# 05-AD9546_StrapsXtal.net
KiCad netlist of a schematic drawn in Altium Designer
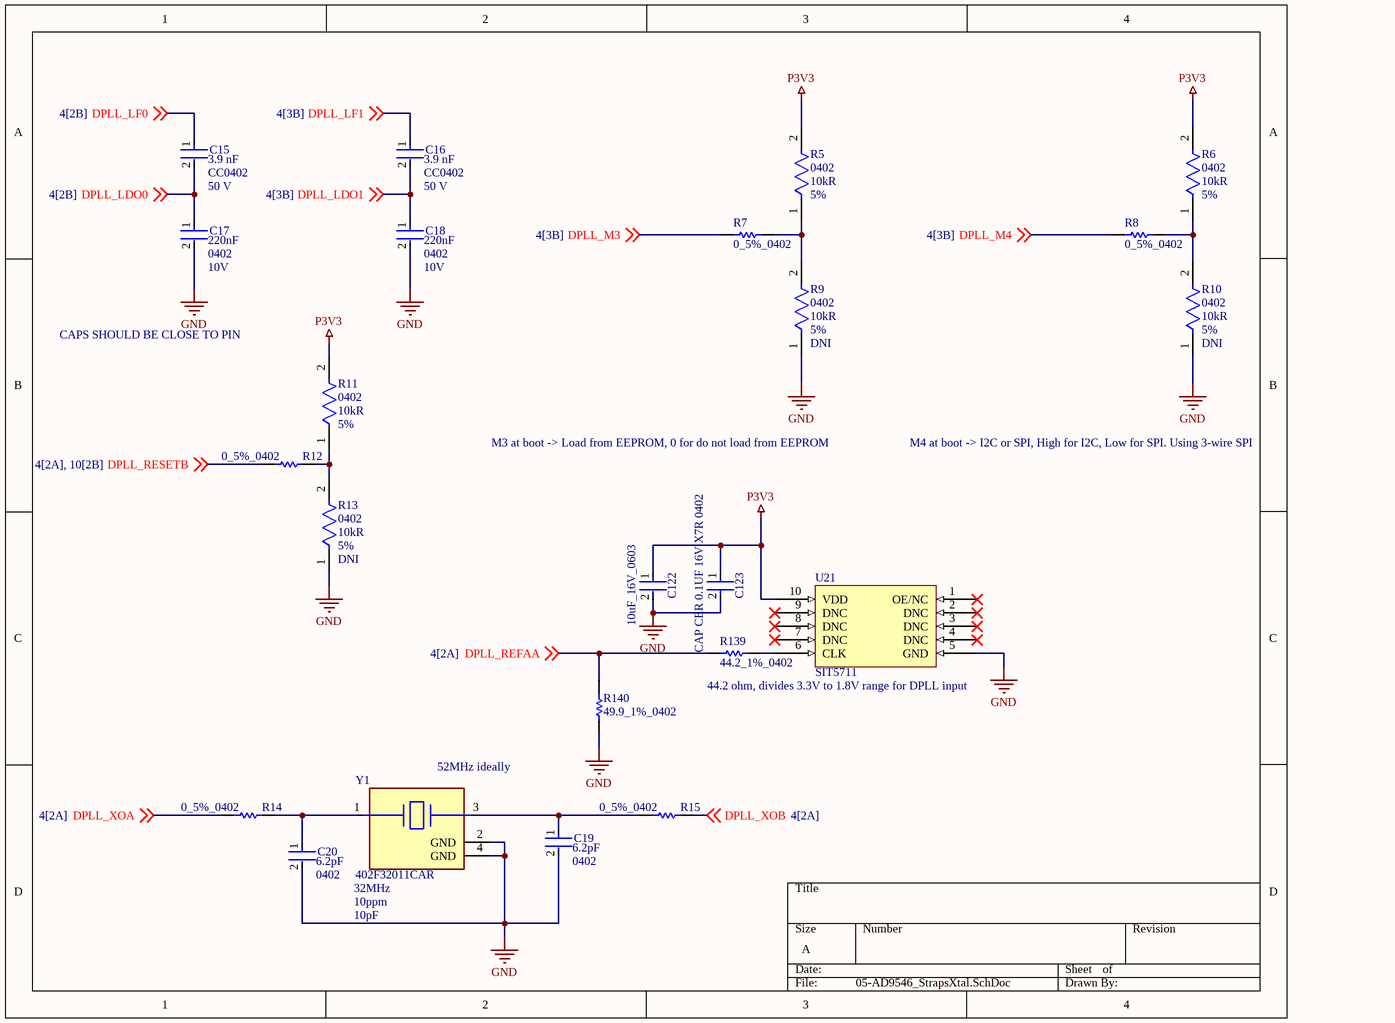
[diagram p0: 05-AD9546_StrapsXtal.SchDoc]

(export (version "E")
  (design (tool "Eeschema 10.0.6"))
  (components
    (comp (ref "C15")
      (value "3.9 nF")
      (footprint "FP-CC0402-MFG")
      (description "CAP CER 3900PF 50V X7R 0402")
      (fields
        (field (name "OCTOPART") "https://octopart.com/cc0402krx7r9bb392-yageo-9291741")
        (field (name "TOLERANCE") "0.1")
        (field (name "VOLTAGE RATING") "50 V")
        (field (name "PACKAGE") "CC0402")
      )
      (libsource (lib "Altium Content Vault") (part "11868f565c42a9108669ba33697ecf6"))
    )
    (comp (ref "C16")
      (value "3.9 nF")
      (footprint "FP-CC0402-MFG")
      (description "CAP CER 3900PF 50V X7R 0402")
      (fields
        (field (name "OCTOPART") "https://octopart.com/cc0402krx7r9bb392-yageo-9291741")
        (field (name "TOLERANCE") "0.1")
        (field (name "VOLTAGE RATING") "50 V")
        (field (name "PACKAGE") "CC0402")
      )
      (libsource (lib "Altium Content Vault") (part "11868f565c42a9108669ba33697ecf6"))
    )
    (comp (ref "C17")
      (value "GRM155R61A224KE19D")
      (footprint "FP-GRM155-0_05-IPC_A")
      (description "CAP CER 0.22UF 10V X5R 0402")
      (fields
        (field (name "VOLTAGE") "10V")
        (field (name "TOLERANCE") "10%")
        (field (name "CASE/PACKAGE") "0402")
        (field (name "CAPACITANCE") "220nF")
      )
      (libsource (lib "Altium Content Vault") (part "02cd4be3c70576c341d710602a673aa"))
    )
    (comp (ref "C18")
      (value "GRM155R61A224KE19D")
      (footprint "FP-GRM155-0_05-IPC_A")
      (description "CAP CER 0.22UF 10V X5R 0402")
      (fields
        (field (name "VOLTAGE") "10V")
        (field (name "TOLERANCE") "10%")
        (field (name "CASE/PACKAGE") "0402")
        (field (name "CAPACITANCE") "220nF")
      )
      (libsource (lib "Altium Content Vault") (part "02cd4be3c70576c341d710602a673aa"))
    )
    (comp (ref "C19")
      (value "CL05C6R2CB5NNNC")
      (footprint "FP-CL468-IPC_C")
      (description "Cap Ceramic 6.2pF 50V C0G ±0.25pF SMD 0402 +125°C Paper T/R")
      (fields (field (name "CASE/PACKAGE") "0402") (field (name "CAPACITANCE") "6.2pF"))
      (libsource (lib "Altium Content Vault") (part "b4654b650e69147ec39a6b967a45e02"))
    )
    (comp (ref "C20")
      (value "CL05C6R2CB5NNNC")
      (footprint "FP-CL468-IPC_C")
      (description "Cap Ceramic 6.2pF 50V C0G ±0.25pF SMD 0402 +125°C Paper T/R")
      (fields (field (name "CASE/PACKAGE") "0402") (field (name "CAPACITANCE") "6.2pF"))
      (libsource (lib "Altium Content Vault") (part "b4654b650e69147ec39a6b967a45e02"))
    )
    (comp (ref "C122")
      (value "10uF_16V_0603")
      (footprint "FP-C1608-MFG")
      (description "CAP CER 10UF 16V X5R 0603")
      (fields
        (field (name "OCTOPART") "https://octopart.com/c1608x5r1c106m080ab-tdk-26013480")
        (field (name "MANUFACTURER") "TDK Corporation")
      )
      (libsource (lib "Altium Content Vault") (part "11868f565c42a9108669ba33697ecf6"))
    )
    (comp (ref "C123")
      (value "GRM155R71C104KA88D")
      (footprint "FP-GRM15-MFG")
      (description "CAP CER 0.1UF 16V X7R 0402")
      (fields
        (field (name "TOLERANCE") "10%")
        (field (name "OCTOPART") "https://octopart.com/grm155r71c104ka88d-murata-196880")
        (field (name "DIGIKEY DESCRIPTION") "CAP CER 0.1UF 16V X7R 0402")
      )
      (libsource (lib "Altium Content Vault") (part "236180d848d6139a670b325ea6854c9"))
    )
    (comp (ref "R5")
      (value "CRCW040210K0JNED")
      (footprint "FP-CRCW0402-e3-IPC_B")
      (description "RES Thick Film, 10kΩ, 5%, 0.063W, 200ppm/°C, 0402")
      (fields
        (field (name "CASE/PACKAGE") "0402")
        (field (name "RESISTANCE") "10kR")
        (field (name "TOLERANCE") "5%")
      )
      (libsource (lib "Altium Content Vault") (part "1029c3af85768c4190bb7ad29bc67b5"))
    )
    (comp (ref "R6")
      (value "CRCW040210K0JNED")
      (footprint "FP-CRCW0402-e3-IPC_B")
      (description "RES Thick Film, 10kΩ, 5%, 0.063W, 200ppm/°C, 0402")
      (fields
        (field (name "CASE/PACKAGE") "0402")
        (field (name "RESISTANCE") "10kR")
        (field (name "TOLERANCE") "5%")
      )
      (libsource (lib "Altium Content Vault") (part "1029c3af85768c4190bb7ad29bc67b5"))
    )
    (comp (ref "R7")
      (value "0_5%_0402")
      (footprint "RESC1005X40X25ML05T10")
      (fields (field (name "PART NUMBER") "CRCW04020000Z0EDHP") (field (name "MANUFACTURER") "Vishay Dale"))
      (libsource (lib "Altium Content Vault") (part "RES"))
    )
    (comp (ref "R8")
      (value "0_5%_0402")
      (footprint "RESC1005X40X25ML05T10")
      (fields (field (name "PART NUMBER") "CRCW04020000Z0EDHP") (field (name "MANUFACTURER") "Vishay Dale"))
      (libsource (lib "Altium Content Vault") (part "RES"))
    )
    (comp (ref "R9")
      (value "CRCW040210K0JNED")
      (footprint "FP-CRCW0402-e3-IPC_B")
      (description "RES Thick Film, 10kΩ, 5%, 0.063W, 200ppm/°C, 0402")
      (fields
        (field (name "CASE/PACKAGE") "0402")
        (field (name "RESISTANCE") "10kR")
        (field (name "TOLERANCE") "5%")
        (field (name "DNI") "DNI")
      )
      (libsource (lib "Altium Content Vault") (part "1029c3af85768c4190bb7ad29bc67b5"))
    )
    (comp (ref "R10")
      (value "CRCW040210K0JNED")
      (footprint "FP-CRCW0402-e3-IPC_B")
      (description "RES Thick Film, 10kΩ, 5%, 0.063W, 200ppm/°C, 0402")
      (fields
        (field (name "CASE/PACKAGE") "0402")
        (field (name "RESISTANCE") "10kR")
        (field (name "TOLERANCE") "5%")
        (field (name "DNI") "DNI")
      )
      (libsource (lib "Altium Content Vault") (part "1029c3af85768c4190bb7ad29bc67b5"))
    )
    (comp (ref "R11")
      (value "CRCW040210K0JNED")
      (footprint "FP-CRCW0402-e3-IPC_B")
      (description "RES Thick Film, 10kΩ, 5%, 0.063W, 200ppm/°C, 0402")
      (fields
        (field (name "CASE/PACKAGE") "0402")
        (field (name "RESISTANCE") "10kR")
        (field (name "TOLERANCE") "5%")
      )
      (libsource (lib "Altium Content Vault") (part "1029c3af85768c4190bb7ad29bc67b5"))
    )
    (comp (ref "R12")
      (value "0_5%_0402")
      (footprint "RESC1005X40X25LL10T10")
      (fields (field (name "MANUFACTURER") "KOA Speer") (field (name "PART NUMBER") "RK73Z1ETTP"))
      (libsource (lib "Altium Content Vault") (part "RES"))
    )
    (comp (ref "R13")
      (value "CRCW040210K0JNED")
      (footprint "FP-CRCW0402-e3-IPC_B")
      (description "RES Thick Film, 10kΩ, 5%, 0.063W, 200ppm/°C, 0402")
      (fields
        (field (name "CASE/PACKAGE") "0402")
        (field (name "RESISTANCE") "10kR")
        (field (name "TOLERANCE") "5%")
        (field (name "DNI") "DNI")
      )
      (libsource (lib "Altium Content Vault") (part "1029c3af85768c4190bb7ad29bc67b5"))
    )
    (comp (ref "R14")
      (value "0_5%_0402")
      (footprint "RESC1005X40X25LL10T10")
      (fields (field (name "MANUFACTURER") "KOA Speer") (field (name "PART NUMBER") "RK73Z1ETTP"))
      (libsource (lib "Altium Content Vault") (part "RES"))
    )
    (comp (ref "R15")
      (value "0_5%_0402")
      (footprint "RESC1005X40X25LL10T10")
      (fields (field (name "MANUFACTURER") "KOA Speer") (field (name "PART NUMBER") "RK73Z1ETTP"))
      (libsource (lib "Altium Content Vault") (part "RES"))
    )
    (comp (ref "R139")
      (value "44.2_1%_0402")
      (footprint "RESC0402(1005)_M")
      (description "44R2 0.063W 1% 0402 (1005 Metric)  SMD")
      (fields (field (name "TOLERANCE") "1 %") (field (name "POWER") "0.063 W"))
      (libsource (lib "Altium Content Vault") (part "RES"))
    )
    (comp (ref "R140")
      (value "49.9_1%_0402")
      (footprint "RESC1005X40X25NL05T05")
      (fields (field (name "MANUFACTURER") "Panasonic") (field (name "PART NUMBER") "ERJ-2RKF49R9X"))
      (libsource (lib "Altium Content Vault") (part "RES"))
    )
    (comp (ref "U21")
      (value "SIT5711")
      (footprint "SIT5711")
      (libsource (lib "TimeDrive_Lib") (part "SIT5711"))
    )
    (comp (ref "Y1")
      (value "402F32011CAR")
      (footprint "FP-402-MFG")
      (description "CRYSTAL 32.0000MHZ 10PF SMD")
      (fields
        (field (name "FREQUENCY") "32MHz")
        (field (name "FREQUENCY STABILITY") "10ppm")
        (field (name "TOLERANCE") "10ppm")
        (field (name "LOAD CAPACITANCE") "10pF")
      )
      (libsource (lib "Altium Content Vault") (part "aa2bcc763e4d5c877d8ff97ea4c95a3"))
    )
  )
  (nets
    (net (code "1") (name "DPLL_LDO0") (class "Default")
      (node (ref "C15") (pin "2") (pinfunction "2_2") (pintype "passive"))
      (node (ref "C17") (pin "1") (pinfunction "1_1") (pintype "passive"))
    )
    (net (code "2") (name "DPLL_LDO1") (class "Default")
      (node (ref "C16") (pin "2") (pinfunction "2_2") (pintype "passive"))
      (node (ref "C18") (pin "1") (pinfunction "1_1") (pintype "passive"))
    )
    (net (code "3") (name "DPLL_LF0") (class "Default")
      (node (ref "C15") (pin "1") (pinfunction "1_1") (pintype "passive"))
    )
    (net (code "4") (name "DPLL_LF1") (class "Default")
      (node (ref "C16") (pin "1") (pinfunction "1_1") (pintype "passive"))
    )
    (net (code "5") (name "DPLL_M3") (class "Default")
      (node (ref "R7") (pin "1") (pinfunction "1_1") (pintype "passive"))
    )
    (net (code "6") (name "DPLL_M4") (class "Default")
      (node (ref "R8") (pin "1") (pinfunction "1_1") (pintype "passive"))
    )
    (net (code "7") (name "DPLL_REFAA") (class "Default")
      (node (ref "R139") (pin "1") (pinfunction "1_1") (pintype "passive"))
      (node (ref "R140") (pin "2") (pinfunction "2_2") (pintype "passive"))
    )
    (net (code "8") (name "DPLL_RESETB") (class "Default")
      (node (ref "R12") (pin "1") (pinfunction "1_1") (pintype "passive"))
    )
    (net (code "9") (name "DPLL_XOA") (class "Default")
      (node (ref "R14") (pin "1") (pinfunction "1_1") (pintype "passive"))
    )
    (net (code "10") (name "DPLL_XOB") (class "Default")
      (node (ref "R15") (pin "2") (pinfunction "2_2") (pintype "passive"))
    )
    (net (code "11") (name "GND") (class "Default")
      (node (ref "C122") (pin "2") (pinfunction "2_2") (pintype "passive"))
      (node (ref "C123") (pin "2") (pinfunction "2_2") (pintype "passive"))
      (node (ref "C17") (pin "2") (pinfunction "2_2") (pintype "passive"))
      (node (ref "C18") (pin "2") (pinfunction "2_2") (pintype "passive"))
      (node (ref "C19") (pin "2") (pinfunction "2_2") (pintype "passive"))
      (node (ref "C20") (pin "2") (pinfunction "2_2") (pintype "passive"))
      (node (ref "R10") (pin "1") (pinfunction "1_1") (pintype "passive"))
      (node (ref "R13") (pin "1") (pinfunction "1_1") (pintype "passive"))
      (node (ref "R140") (pin "1") (pinfunction "1_1") (pintype "passive"))
      (node (ref "R9") (pin "1") (pinfunction "1_1") (pintype "passive"))
      (node (ref "U21") (pin "5") (pinfunction "GND_5") (pintype "input"))
      (node (ref "Y1") (pin "2") (pinfunction "GND_2") (pintype "power_in"))
      (node (ref "Y1") (pin "4") (pinfunction "GND_4") (pintype "power_in"))
    )
    (net (code "12") (name "Net-(C19-Pad1)") (class "Default")
      (node (ref "C19") (pin "1") (pinfunction "1_1") (pintype "passive"))
      (node (ref "R15") (pin "1") (pinfunction "1_1") (pintype "passive"))
      (node (ref "Y1") (pin "3") (pinfunction "3_3") (pintype "passive"))
    )
    (net (code "13") (name "Net-(C20-Pad1)") (class "Default")
      (node (ref "C20") (pin "1") (pinfunction "1_1") (pintype "passive"))
      (node (ref "R14") (pin "2") (pinfunction "2_2") (pintype "passive"))
      (node (ref "Y1") (pin "1") (pinfunction "1_1") (pintype "passive"))
    )
    (net (code "14") (name "Net-(R5-Pad1)") (class "Default")
      (node (ref "R5") (pin "1") (pinfunction "1_1") (pintype "passive"))
      (node (ref "R7") (pin "2") (pinfunction "2_2") (pintype "passive"))
      (node (ref "R9") (pin "2") (pinfunction "2_2") (pintype "passive"))
    )
    (net (code "15") (name "Net-(R10-Pad2)") (class "Default")
      (node (ref "R10") (pin "2") (pinfunction "2_2") (pintype "passive"))
      (node (ref "R6") (pin "1") (pinfunction "1_1") (pintype "passive"))
      (node (ref "R8") (pin "2") (pinfunction "2_2") (pintype "passive"))
    )
    (net (code "16") (name "Net-(R11-Pad1)") (class "Default")
      (node (ref "R11") (pin "1") (pinfunction "1_1") (pintype "passive"))
      (node (ref "R12") (pin "2") (pinfunction "2_2") (pintype "passive"))
      (node (ref "R13") (pin "2") (pinfunction "2_2") (pintype "passive"))
    )
    (net (code "17") (name "Net-(U21-CLK)") (class "Default")
      (node (ref "R139") (pin "2") (pinfunction "2_2") (pintype "passive"))
      (node (ref "U21") (pin "6") (pinfunction "CLK_6") (pintype "input"))
    )
    (net (code "18") (name "P3V3") (class "Default")
      (node (ref "C122") (pin "1") (pinfunction "1_1") (pintype "passive"))
      (node (ref "C123") (pin "1") (pinfunction "1_1") (pintype "passive"))
      (node (ref "R11") (pin "2") (pinfunction "2_2") (pintype "passive"))
      (node (ref "R5") (pin "2") (pinfunction "2_2") (pintype "passive"))
      (node (ref "R6") (pin "2") (pinfunction "2_2") (pintype "passive"))
      (node (ref "U21") (pin "10") (pinfunction "VDD_10") (pintype "input"))
    )
    (net (code "19") (name "unconnected-(U21-DNC-Pad2)") (class "Default")
      (node (ref "U21") (pin "2") (pinfunction "DNC_2") (pintype "input+no_connect"))
    )
    (net (code "20") (name "unconnected-(U21-DNC-Pad3)") (class "Default")
      (node (ref "U21") (pin "3") (pinfunction "DNC_3") (pintype "input+no_connect"))
    )
    (net (code "21") (name "unconnected-(U21-DNC-Pad4)") (class "Default")
      (node (ref "U21") (pin "4") (pinfunction "DNC_4") (pintype "input+no_connect"))
    )
    (net (code "22") (name "unconnected-(U21-DNC-Pad7)") (class "Default")
      (node (ref "U21") (pin "7") (pinfunction "DNC_7") (pintype "input+no_connect"))
    )
    (net (code "23") (name "unconnected-(U21-DNC-Pad8)") (class "Default")
      (node (ref "U21") (pin "8") (pinfunction "DNC_8") (pintype "input+no_connect"))
    )
    (net (code "24") (name "unconnected-(U21-DNC-Pad9)") (class "Default")
      (node (ref "U21") (pin "9") (pinfunction "DNC_9") (pintype "input+no_connect"))
    )
    (net (code "25") (name "unconnected-(U21-OE{slash}NC-Pad1)") (class "Default")
      (node (ref "U21") (pin "1") (pinfunction "OE/NC_1") (pintype "input+no_connect"))
    )
  )
)
